# PowerTree.net
KiCad netlist of a schematic drawn in Altium Designer
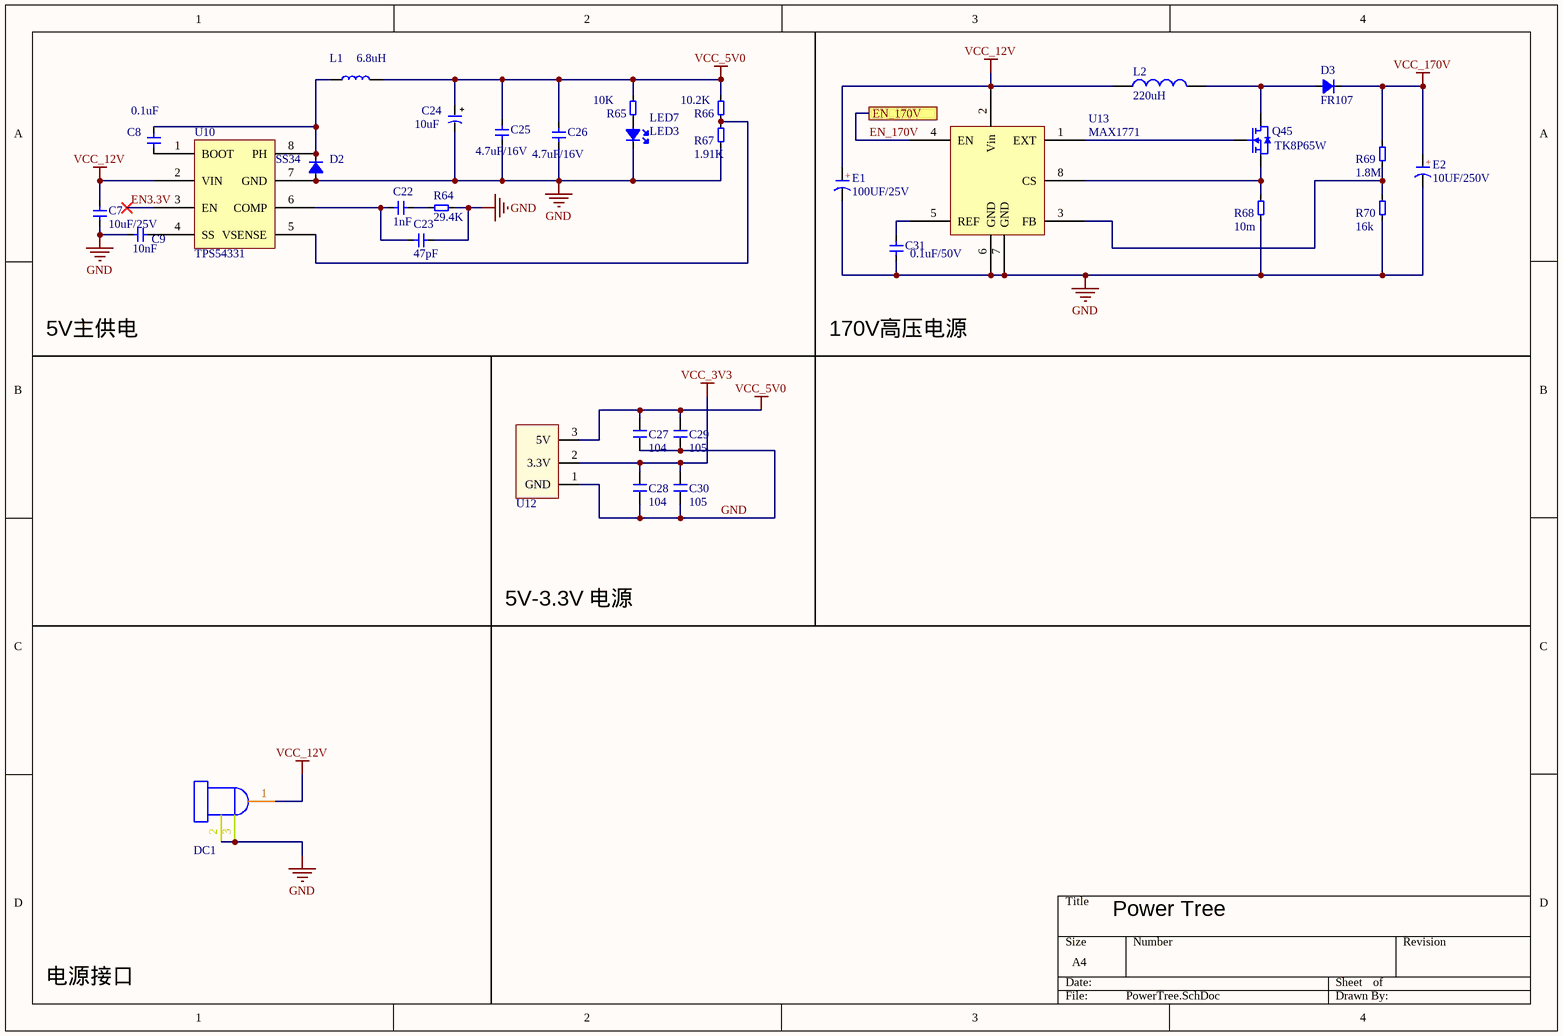
[diagram p0: PowerTree.SchDoc]

(export (version "E")
  (design (tool "Eeschema 10.0.6"))
  (components
    (comp (ref "C7")
      (value "10uF/25V")
      (footprint "1206")
      (description "Capacitor")
      (libsource (lib "HXT-SCH") (part "CAP1"))
    )
    (comp (ref "C8")
      (value "0.1uF")
      (footprint "0603C")
      (description "Capacitor")
      (libsource (lib "HXT-SCH") (part "CAP1"))
    )
    (comp (ref "C9")
      (value "10nF")
      (footprint "0603C")
      (description "Capacitor")
      (libsource (lib "YHT-PCB") (part "CAP"))
    )
    (comp (ref "C22")
      (value "1nF")
      (footprint "0603C")
      (description "Capacitor")
      (libsource (lib "HXT-SCH") (part "CAP1"))
    )
    (comp (ref "C23")
      (value "47pF")
      (footprint "0603C")
      (description "Capacitor")
      (libsource (lib "YHT-PCB") (part "CAP"))
    )
    (comp (ref "C24")
      (value "10uF")
      (footprint "3528")
      (description "Capacitor")
      (libsource (lib "YHT-SCH") (part "CAP-+"))
    )
    (comp (ref "C25")
      (value "4.7uF/16V")
      (footprint "0603C")
      (description "Capacitor")
      (libsource (lib "YHT-PCB") (part "CAP"))
    )
    (comp (ref "C26")
      (value "4.7uF/16V")
      (footprint "0603C")
      (description "Capacitor")
      (libsource (lib "YHT-PCB") (part "CAP"))
    )
    (comp (ref "C27")
      (value "104")
      (footprint "C 0805")
      (description "无极性贴片电容")
      (fields (field (name "版权归属") "源创客"))
      (libsource (lib "电阻-电容-电感") (part "C"))
    )
    (comp (ref "C28")
      (value "104")
      (footprint "C 0805")
      (description "无极性贴片电容")
      (fields (field (name "版权归属") "源创客"))
      (libsource (lib "电阻-电容-电感") (part "C"))
    )
    (comp (ref "C29")
      (value "105")
      (footprint "C 0805")
      (description "无极性贴片电容")
      (fields (field (name "版权归属") "源创客"))
      (libsource (lib "电阻-电容-电感") (part "C"))
    )
    (comp (ref "C30")
      (value "105")
      (footprint "C 0805")
      (description "无极性贴片电容")
      (fields (field (name "版权归属") "源创客"))
      (libsource (lib "电阻-电容-电感") (part "C"))
    )
    (comp (ref "C31")
      (value "0.1uF/50V")
      (footprint "0603C")
      (description "Capacitor")
      (libsource (lib "YHT-PCB") (part "CAP"))
    )
    (comp (ref "D2")
      (value "SS34")
      (footprint "DO-214AC-SMA")
      (description "DIODE LED")
      (libsource (lib "HXT-SCH") (part "DIOLED_1"))
    )
    (comp (ref "D3")
      (value "FR107")
      (footprint "DO-214AC-SMA")
      (description "DIODE LED")
      (libsource (lib "HXT-SCH") (part "DIOLED_1"))
    )
    (comp (ref "DC1") (value "DC") (footprint "DC-005") (libsource (lib "QT") (part "DC")))
    (comp (ref "E1")
      (value "100UF/25V")
      (footprint "CM D(6.3*7.7)")
      (description "直插固态电容")
      (fields (field (name "版权归属") "源创客"))
      (libsource (lib "电阻-电容-电感") (part "C-CS"))
    )
    (comp (ref "E2")
      (value "10UF/250V")
      (footprint "CM D(6.3*7.7)")
      (description "直插固态电容")
      (fields (field (name "版权归属") "源创客"))
      (libsource (lib "电阻-电容-电感") (part "C-CS"))
    )
    (comp (ref "L1") (value "6.8uH") (footprint "L100") (libsource (lib "HXT-SCH") (part "INDUCTOR1_1")))
    (comp (ref "L2")
      (value "220uH")
      (footprint "CDRH125")
      (description "小功率贴片电感")
      (fields (field (name "版权归属") "源创客"))
      (libsource (lib "电阻-电容-电感") (part "L"))
    )
    (comp (ref "LED7")
      (value "LED3")
      (footprint "0603-led")
      (description "DIODE LED")
      (libsource (lib "HXT-SCH") (part "CP_DIOLED"))
    )
    (comp (ref "Q45")
      (value "TK8P65W")
      (footprint "D-PAK")
      (description "P-channel Enhancement Mode MOSFET")
      (fields (field (name "PUBLISHER") "Altium Limited"))
      (libsource (lib "HXT-SCH") (part "MOSFET-N"))
    )
    (comp (ref "R64") (value "29.4K") (footprint "0603") (libsource (lib "HXT-SCH") (part "RES2")))
    (comp (ref "R65") (value "10K") (footprint "0603") (libsource (lib "HXT-SCH") (part "RES2")))
    (comp (ref "R66") (value "10.2K") (footprint "0603") (libsource (lib "HXT-SCH") (part "RES2")))
    (comp (ref "R67") (value "1.91K") (footprint "0603") (libsource (lib "HXT-SCH") (part "RES2")))
    (comp (ref "R68") (value "10m") (footprint "R 1206_L") (libsource (lib "HXT-SCH") (part "RES2")))
    (comp (ref "R69") (value "1.8M") (footprint "0603") (libsource (lib "HXT-SCH") (part "RES2")))
    (comp (ref "R70") (value "16k") (footprint "0603") (libsource (lib "HXT-SCH") (part "RES2")))
    (comp (ref "U10") (value "TPS54331") (footprint "SO08") (libsource (lib "YHT-SCH") (part "TPS54331")))
    (comp (ref "U12") (value "LM1117") (footprint "SOT223") (libsource (lib "常用元件库") (part "LM1117")))
    (comp (ref "U13") (value "MAX1771") (footprint "SOP8") (libsource (lib "吴原理图库") (part "MAX1771")))
  )
  (nets
    (net (code "1") (name "/EN3.3V") (class "Default")
      (node (ref "U10") (pin "3") (pinfunction "EN_3") (pintype "passive+no_connect"))
    )
    (net (code "2") (name "/EN_170V") (class "Default")
      (node (ref "U13") (pin "4") (pinfunction "EN_4") (pintype "passive"))
    )
    (net (code "3") (name "GND") (class "Default")
      (node (ref "C23") (pin "2") (pinfunction "2_2") (pintype "passive"))
      (node (ref "C24") (pin "2") (pinfunction "2_2") (pintype "passive"))
      (node (ref "C25") (pin "1") (pinfunction "1_1") (pintype "passive"))
      (node (ref "C26") (pin "1") (pinfunction "1_1") (pintype "passive"))
      (node (ref "C27") (pin "1") (pinfunction "1_1") (pintype "passive"))
      (node (ref "C28") (pin "1") (pinfunction "1_1") (pintype "passive"))
      (node (ref "C29") (pin "2") (pinfunction "2_2") (pintype "passive"))
      (node (ref "C30") (pin "2") (pinfunction "2_2") (pintype "passive"))
      (node (ref "C31") (pin "1") (pinfunction "1_1") (pintype "passive"))
      (node (ref "C7") (pin "1") (pinfunction "1_1") (pintype "passive"))
      (node (ref "C9") (pin "2") (pinfunction "2_2") (pintype "passive"))
      (node (ref "D2") (pin "1") (pinfunction "A_1") (pintype "passive"))
      (node (ref "DC1") (pin "2") (pinfunction "-_2") (pintype "passive"))
      (node (ref "DC1") (pin "3") (pinfunction "-_3") (pintype "passive"))
      (node (ref "E1") (pin "2") (pinfunction "K_2") (pintype "passive"))
      (node (ref "E2") (pin "2") (pinfunction "K_2") (pintype "passive"))
      (node (ref "LED7") (pin "2") (pinfunction "K_2") (pintype "passive"))
      (node (ref "R64") (pin "1") (pinfunction "1_1") (pintype "passive"))
      (node (ref "R67") (pin "1") (pinfunction "1_1") (pintype "passive"))
      (node (ref "R68") (pin "1") (pinfunction "1_1") (pintype "passive"))
      (node (ref "R70") (pin "1") (pinfunction "1_1") (pintype "passive"))
      (node (ref "U10") (pin "7") (pinfunction "GND_7") (pintype "passive"))
      (node (ref "U12") (pin "1") (pinfunction "GND_1") (pintype "passive"))
      (node (ref "U13") (pin "6") (pinfunction "GND_6") (pintype "passive"))
      (node (ref "U13") (pin "7") (pinfunction "GND_7") (pintype "passive"))
    )
    (net (code "4") (name "Net-(C22-Pad1)") (class "Default")
      (node (ref "C22") (pin "1") (pinfunction "1_1") (pintype "passive"))
      (node (ref "R64") (pin "2") (pinfunction "2_2") (pintype "passive"))
    )
    (net (code "5") (name "Net-(D2-K)") (class "Default")
      (node (ref "C8") (pin "2") (pinfunction "2_2") (pintype "passive"))
      (node (ref "D2") (pin "2") (pinfunction "K_2") (pintype "passive"))
      (node (ref "L1") (pin "2") (pinfunction "2_2") (pintype "passive"))
      (node (ref "U10") (pin "8") (pinfunction "PH_8") (pintype "power_in"))
    )
    (net (code "6") (name "Net-(D3-A)") (class "Default")
      (node (ref "D3") (pin "1") (pinfunction "A_1") (pintype "passive"))
      (node (ref "L2") (pin "2") (pinfunction "2_2") (pintype "passive"))
      (node (ref "Q45") (pin "3") (pinfunction "D_3") (pintype "passive"))
    )
    (net (code "7") (name "Net-(LED7-A)") (class "Default")
      (node (ref "LED7") (pin "1") (pinfunction "A_1") (pintype "passive"))
      (node (ref "R65") (pin "1") (pinfunction "1_1") (pintype "passive"))
    )
    (net (code "8") (name "Net-(Q45-G)") (class "Default")
      (node (ref "Q45") (pin "1") (pinfunction "G_1") (pintype "passive"))
      (node (ref "U13") (pin "1") (pinfunction "EXT_1") (pintype "passive"))
    )
    (net (code "9") (name "Net-(Q45-S)") (class "Default")
      (node (ref "Q45") (pin "2") (pinfunction "S_2") (pintype "passive"))
      (node (ref "R68") (pin "2") (pinfunction "2_2") (pintype "passive"))
      (node (ref "U13") (pin "8") (pinfunction "CS_8") (pintype "passive"))
    )
    (net (code "10") (name "Net-(U10-BOOT)") (class "Default")
      (node (ref "C8") (pin "1") (pinfunction "1_1") (pintype "passive"))
      (node (ref "U10") (pin "1") (pinfunction "BOOT_1") (pintype "passive"))
    )
    (net (code "11") (name "Net-(U10-COMP)") (class "Default")
      (node (ref "C22") (pin "2") (pinfunction "2_2") (pintype "passive"))
      (node (ref "C23") (pin "1") (pinfunction "1_1") (pintype "passive"))
      (node (ref "U10") (pin "6") (pinfunction "COMP_6") (pintype "passive"))
    )
    (net (code "12") (name "Net-(U10-SS)") (class "Default")
      (node (ref "C9") (pin "1") (pinfunction "1_1") (pintype "passive"))
      (node (ref "U10") (pin "4") (pinfunction "SS_4") (pintype "power_in"))
    )
    (net (code "13") (name "Net-(U10-VSENSE)") (class "Default")
      (node (ref "R66") (pin "1") (pinfunction "1_1") (pintype "passive"))
      (node (ref "R67") (pin "2") (pinfunction "2_2") (pintype "passive"))
      (node (ref "U10") (pin "5") (pinfunction "VSENSE_5") (pintype "passive"))
    )
    (net (code "14") (name "Net-(U13-FB)") (class "Default")
      (node (ref "R69") (pin "1") (pinfunction "1_1") (pintype "passive"))
      (node (ref "R70") (pin "2") (pinfunction "2_2") (pintype "passive"))
      (node (ref "U13") (pin "3") (pinfunction "FB_3") (pintype "passive"))
    )
    (net (code "15") (name "Net-(U13-REF)") (class "Default")
      (node (ref "C31") (pin "2") (pinfunction "2_2") (pintype "passive"))
      (node (ref "U13") (pin "5") (pinfunction "REF_5") (pintype "passive"))
    )
    (net (code "16") (name "VCC_3V3") (class "Default")
      (node (ref "C28") (pin "2") (pinfunction "2_2") (pintype "passive"))
      (node (ref "C30") (pin "1") (pinfunction "1_1") (pintype "passive"))
      (node (ref "U12") (pin "2") (pinfunction "3.3V_2") (pintype "passive"))
    )
    (net (code "17") (name "VCC_5V0") (class "Default")
      (node (ref "C24") (pin "1") (pinfunction "1_1") (pintype "passive"))
      (node (ref "C25") (pin "2") (pinfunction "2_2") (pintype "passive"))
      (node (ref "C26") (pin "2") (pinfunction "2_2") (pintype "passive"))
      (node (ref "C27") (pin "2") (pinfunction "2_2") (pintype "passive"))
      (node (ref "C29") (pin "1") (pinfunction "1_1") (pintype "passive"))
      (node (ref "L1") (pin "1") (pinfunction "1_1") (pintype "passive"))
      (node (ref "R65") (pin "2") (pinfunction "2_2") (pintype "passive"))
      (node (ref "R66") (pin "2") (pinfunction "2_2") (pintype "passive"))
      (node (ref "U12") (pin "3") (pinfunction "5V_3") (pintype "passive"))
    )
    (net (code "18") (name "VCC_12V") (class "Default")
      (node (ref "C7") (pin "2") (pinfunction "2_2") (pintype "passive"))
      (node (ref "DC1") (pin "1") (pinfunction "+_1") (pintype "passive"))
      (node (ref "E1") (pin "1") (pinfunction "A_1") (pintype "passive"))
      (node (ref "L2") (pin "1") (pinfunction "1_1") (pintype "passive"))
      (node (ref "U10") (pin "2") (pinfunction "VIN_2") (pintype "passive"))
      (node (ref "U13") (pin "2") (pinfunction "Vin_2") (pintype "passive"))
    )
    (net (code "19") (name "VCC_170V") (class "Default")
      (node (ref "D3") (pin "2") (pinfunction "K_2") (pintype "passive"))
      (node (ref "E2") (pin "1") (pinfunction "A_1") (pintype "passive"))
      (node (ref "R69") (pin "2") (pinfunction "2_2") (pintype "passive"))
    )
  )
)
